# VCO-40106.net
KiCad netlist of a schematic drawn in EAGLE
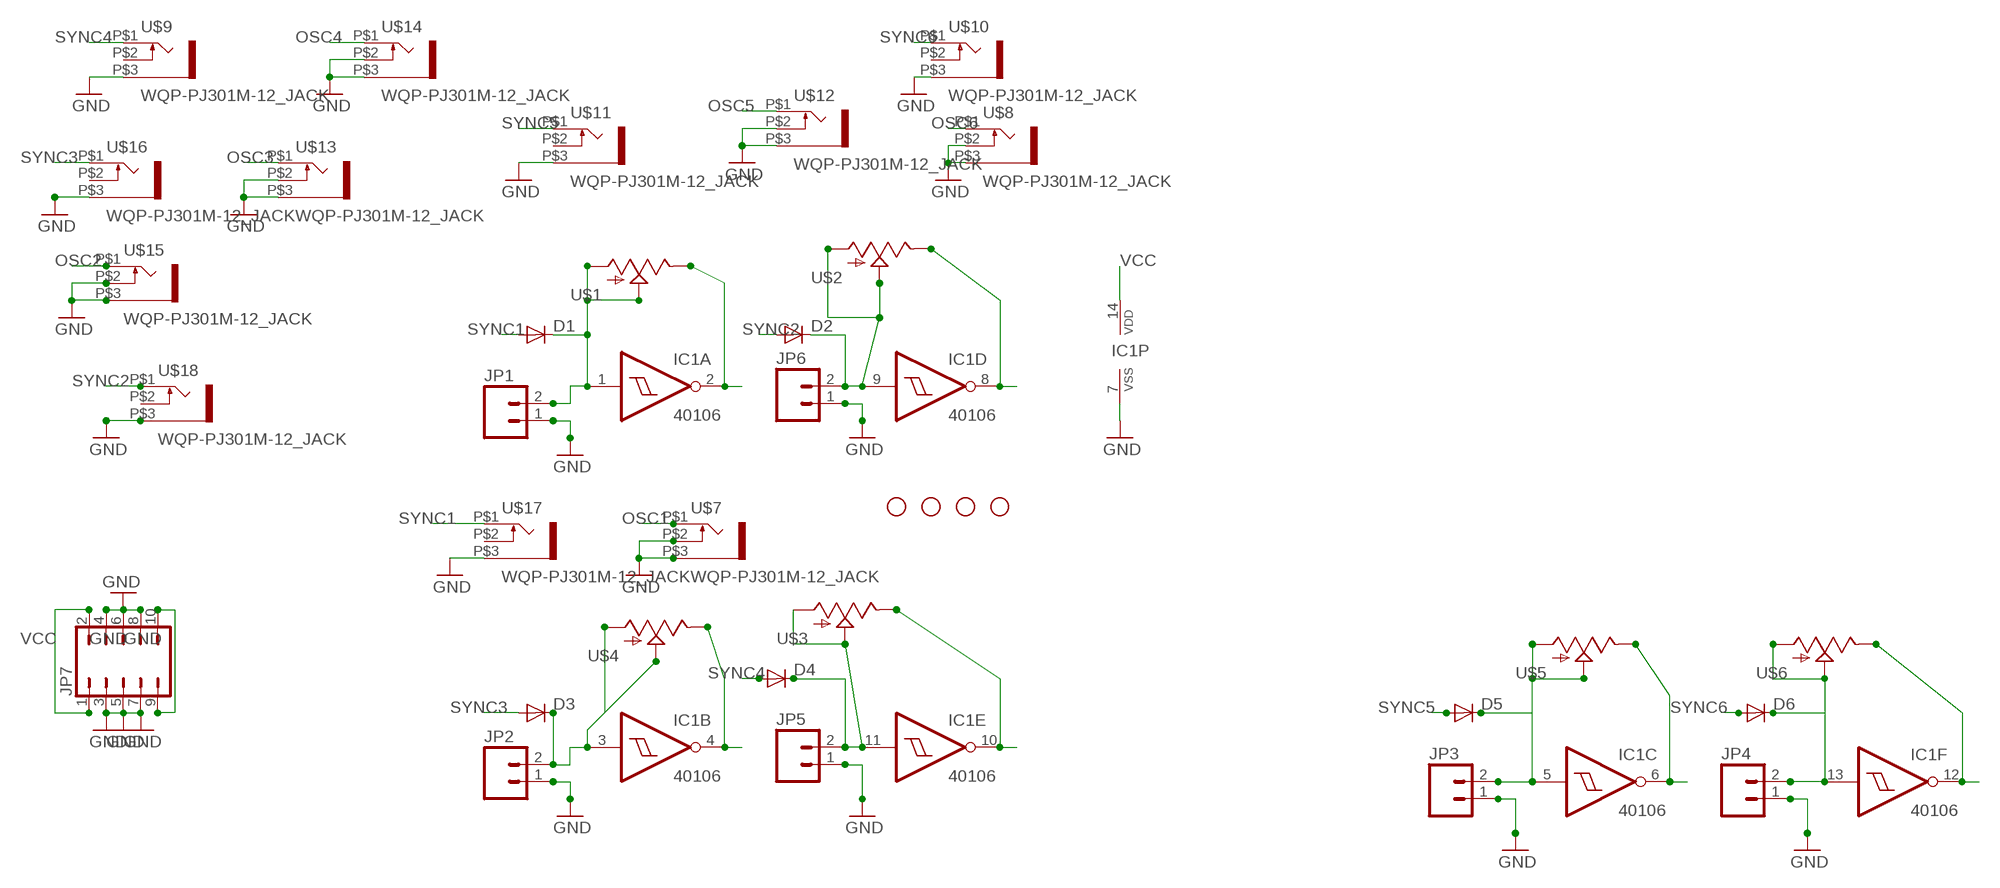
[diagram p0: schematic, sheet 1]

(export (version "E")
  (design (tool "Eeschema 10.0.6"))
  (components
    (comp (ref "D1")
      (value "DIODE1N4148")
      (footprint "eagle-import:DIODE-1N4148")
      (libsource (lib "eagle-import") (part "DIODE1N4148"))
    )
    (comp (ref "D2")
      (value "DIODE1N4148")
      (footprint "eagle-import:DIODE-1N4148")
      (libsource (lib "eagle-import") (part "DIODE1N4148"))
    )
    (comp (ref "D3")
      (value "DIODE1N4148")
      (footprint "eagle-import:DIODE-1N4148")
      (libsource (lib "eagle-import") (part "DIODE1N4148"))
    )
    (comp (ref "D4")
      (value "DIODE1N4148")
      (footprint "eagle-import:DIODE-1N4148")
      (libsource (lib "eagle-import") (part "DIODE1N4148"))
    )
    (comp (ref "D5")
      (value "DIODE1N4148")
      (footprint "eagle-import:DIODE-1N4148")
      (libsource (lib "eagle-import") (part "DIODE1N4148"))
    )
    (comp (ref "D6")
      (value "DIODE1N4148")
      (footprint "eagle-import:DIODE-1N4148")
      (libsource (lib "eagle-import") (part "DIODE1N4148"))
    )
    (comp (ref "IC1")
      (value "40106")
      (footprint "eagle-import:DIL14")
      (libsource (lib "eagle-import") (part "40106N"))
    )
    (comp (ref "JP1")
      (value "M02")
      (footprint "eagle-import:1X02_LONGPADS")
      (libsource (lib "eagle-import") (part "M02"))
    )
    (comp (ref "JP2")
      (value "M02")
      (footprint "eagle-import:1X02_LONGPADS")
      (libsource (lib "eagle-import") (part "M02"))
    )
    (comp (ref "JP3")
      (value "M02")
      (footprint "eagle-import:1X02_LONGPADS")
      (libsource (lib "eagle-import") (part "M02"))
    )
    (comp (ref "JP4")
      (value "M02")
      (footprint "eagle-import:1X02_LONGPADS")
      (libsource (lib "eagle-import") (part "M02"))
    )
    (comp (ref "JP5")
      (value "M02")
      (footprint "eagle-import:1X02_LONGPADS")
      (libsource (lib "eagle-import") (part "M02"))
    )
    (comp (ref "JP6")
      (value "M02")
      (footprint "eagle-import:1X02_LONGPADS")
      (libsource (lib "eagle-import") (part "M02"))
    )
    (comp (ref "JP7")
      (value "JP5Q")
      (footprint "eagle-import:JP5Q")
      (libsource (lib "eagle-import") (part "JP5Q"))
    )
    (comp (ref "JP8")
      (value "STAND-OFF")
      (footprint "eagle-import:STAND-OFF")
      (libsource (lib "eagle-import") (part "STAND-OFF"))
    )
    (comp (ref "JP9")
      (value "STAND-OFF")
      (footprint "eagle-import:STAND-OFF")
      (libsource (lib "eagle-import") (part "STAND-OFF"))
    )
    (comp (ref "JP10")
      (value "STAND-OFF")
      (footprint "eagle-import:STAND-OFF")
      (libsource (lib "eagle-import") (part "STAND-OFF"))
    )
    (comp (ref "JP11")
      (value "STAND-OFF")
      (footprint "eagle-import:STAND-OFF")
      (libsource (lib "eagle-import") (part "STAND-OFF"))
    )
    (comp (ref "U$1")
      (value "POT")
      (footprint "eagle-import:ALPS_POT")
      (libsource (lib "eagle-import") (part "POT"))
    )
    (comp (ref "U$2")
      (value "POT")
      (footprint "eagle-import:ALPS_POT")
      (libsource (lib "eagle-import") (part "POT"))
    )
    (comp (ref "U$3")
      (value "POT")
      (footprint "eagle-import:ALPS_POT")
      (libsource (lib "eagle-import") (part "POT"))
    )
    (comp (ref "U$4")
      (value "POT")
      (footprint "eagle-import:ALPS_POT")
      (libsource (lib "eagle-import") (part "POT"))
    )
    (comp (ref "U$5")
      (value "POT")
      (footprint "eagle-import:ALPS_POT")
      (libsource (lib "eagle-import") (part "POT"))
    )
    (comp (ref "U$6")
      (value "POT")
      (footprint "eagle-import:ALPS_POT")
      (libsource (lib "eagle-import") (part "POT"))
    )
    (comp (ref "U$7")
      (value "WQP-PJ301M-12_JACK")
      (footprint "eagle-import:WQP-PJ301M-12_JACK")
      (libsource (lib "eagle-import") (part "WQP-PJ301M-12_JACK"))
    )
    (comp (ref "U$8")
      (value "WQP-PJ301M-12_JACK")
      (footprint "eagle-import:WQP-PJ301M-12_JACK")
      (libsource (lib "eagle-import") (part "WQP-PJ301M-12_JACK"))
    )
    (comp (ref "U$9")
      (value "WQP-PJ301M-12_JACK")
      (footprint "eagle-import:WQP-PJ301M-12_JACK")
      (libsource (lib "eagle-import") (part "WQP-PJ301M-12_JACK"))
    )
    (comp (ref "U$10")
      (value "WQP-PJ301M-12_JACK")
      (footprint "eagle-import:WQP-PJ301M-12_JACK")
      (libsource (lib "eagle-import") (part "WQP-PJ301M-12_JACK"))
    )
    (comp (ref "U$11")
      (value "WQP-PJ301M-12_JACK")
      (footprint "eagle-import:WQP-PJ301M-12_JACK")
      (libsource (lib "eagle-import") (part "WQP-PJ301M-12_JACK"))
    )
    (comp (ref "U$12")
      (value "WQP-PJ301M-12_JACK")
      (footprint "eagle-import:WQP-PJ301M-12_JACK")
      (libsource (lib "eagle-import") (part "WQP-PJ301M-12_JACK"))
    )
    (comp (ref "U$13")
      (value "WQP-PJ301M-12_JACK")
      (footprint "eagle-import:WQP-PJ301M-12_JACK")
      (libsource (lib "eagle-import") (part "WQP-PJ301M-12_JACK"))
    )
    (comp (ref "U$14")
      (value "WQP-PJ301M-12_JACK")
      (footprint "eagle-import:WQP-PJ301M-12_JACK")
      (libsource (lib "eagle-import") (part "WQP-PJ301M-12_JACK"))
    )
    (comp (ref "U$15")
      (value "WQP-PJ301M-12_JACK")
      (footprint "eagle-import:WQP-PJ301M-12_JACK")
      (libsource (lib "eagle-import") (part "WQP-PJ301M-12_JACK"))
    )
    (comp (ref "U$16")
      (value "WQP-PJ301M-12_JACK")
      (footprint "eagle-import:WQP-PJ301M-12_JACK")
      (libsource (lib "eagle-import") (part "WQP-PJ301M-12_JACK"))
    )
    (comp (ref "U$17")
      (value "WQP-PJ301M-12_JACK")
      (footprint "eagle-import:WQP-PJ301M-12_JACK")
      (libsource (lib "eagle-import") (part "WQP-PJ301M-12_JACK"))
    )
    (comp (ref "U$18")
      (value "WQP-PJ301M-12_JACK")
      (footprint "eagle-import:WQP-PJ301M-12_JACK")
      (libsource (lib "eagle-import") (part "WQP-PJ301M-12_JACK"))
    )
  )
  (nets
    (net (code "1") (name "/OSC1") (class "Default")
      (node (ref "IC1") (pin "2") (pinfunction "O_2") (pintype "output"))
      (node (ref "U$1") (pin "P$1") (pinfunction "E_P$1") (pintype "passive"))
      (node (ref "U$7") (pin "P$1") (pinfunction "2_P$1") (pintype "passive"))
    )
    (net (code "2") (name "/OSC2") (class "Default")
      (node (ref "IC1") (pin "4") (pinfunction "O_4") (pintype "output"))
      (node (ref "U$15") (pin "P$1") (pinfunction "2_P$1") (pintype "passive"))
      (node (ref "U$4") (pin "P$1") (pinfunction "E_P$1") (pintype "passive"))
    )
    (net (code "3") (name "/OSC3") (class "Default")
      (node (ref "IC1") (pin "6") (pinfunction "O_6") (pintype "output"))
      (node (ref "U$13") (pin "P$1") (pinfunction "2_P$1") (pintype "passive"))
      (node (ref "U$5") (pin "P$1") (pinfunction "E_P$1") (pintype "passive"))
    )
    (net (code "4") (name "/OSC4") (class "Default")
      (node (ref "IC1") (pin "8") (pinfunction "O_8") (pintype "output"))
      (node (ref "U$14") (pin "P$1") (pinfunction "2_P$1") (pintype "passive"))
      (node (ref "U$2") (pin "P$1") (pinfunction "E_P$1") (pintype "passive"))
    )
    (net (code "5") (name "/OSC5") (class "Default")
      (node (ref "IC1") (pin "10") (pinfunction "O_10") (pintype "output"))
      (node (ref "U$12") (pin "P$1") (pinfunction "2_P$1") (pintype "passive"))
      (node (ref "U$3") (pin "P$1") (pinfunction "E_P$1") (pintype "passive"))
    )
    (net (code "6") (name "/OSC6") (class "Default")
      (node (ref "IC1") (pin "12") (pinfunction "O_12") (pintype "output"))
      (node (ref "U$6") (pin "P$1") (pinfunction "E_P$1") (pintype "passive"))
      (node (ref "U$8") (pin "P$1") (pinfunction "2_P$1") (pintype "passive"))
    )
    (net (code "7") (name "/SYNC1") (class "Default")
      (node (ref "D1") (pin "A") (pinfunction "A_A") (pintype "passive"))
      (node (ref "U$17") (pin "P$1") (pinfunction "2_P$1") (pintype "passive"))
    )
    (net (code "8") (name "/SYNC2") (class "Default")
      (node (ref "D2") (pin "A") (pinfunction "A_A") (pintype "passive"))
      (node (ref "U$18") (pin "P$1") (pinfunction "2_P$1") (pintype "passive"))
    )
    (net (code "9") (name "/SYNC3") (class "Default")
      (node (ref "D3") (pin "A") (pinfunction "A_A") (pintype "passive"))
      (node (ref "U$16") (pin "P$1") (pinfunction "2_P$1") (pintype "passive"))
    )
    (net (code "10") (name "/SYNC4") (class "Default")
      (node (ref "D4") (pin "A") (pinfunction "A_A") (pintype "passive"))
      (node (ref "U$9") (pin "P$1") (pinfunction "2_P$1") (pintype "passive"))
    )
    (net (code "11") (name "/SYNC5") (class "Default")
      (node (ref "D5") (pin "A") (pinfunction "A_A") (pintype "passive"))
      (node (ref "U$11") (pin "P$1") (pinfunction "2_P$1") (pintype "passive"))
    )
    (net (code "12") (name "/SYNC6") (class "Default")
      (node (ref "D6") (pin "A") (pinfunction "A_A") (pintype "passive"))
      (node (ref "U$10") (pin "P$1") (pinfunction "2_P$1") (pintype "passive"))
    )
    (net (code "13") (name "/VCC") (class "Default")
      (node (ref "IC1") (pin "14") (pinfunction "VDD_14") (pintype "power_in"))
      (node (ref "JP7") (pin "1") (pinfunction "1_1") (pintype "passive"))
      (node (ref "JP7") (pin "2") (pinfunction "2_2") (pintype "passive"))
    )
    (net (code "14") (name "GND") (class "Default")
      (node (ref "IC1") (pin "7") (pinfunction "VSS_7") (pintype "power_in"))
      (node (ref "JP1") (pin "1") (pinfunction "1_1") (pintype "passive"))
      (node (ref "JP2") (pin "1") (pinfunction "1_1") (pintype "passive"))
      (node (ref "JP3") (pin "1") (pinfunction "1_1") (pintype "passive"))
      (node (ref "JP4") (pin "1") (pinfunction "1_1") (pintype "passive"))
      (node (ref "JP5") (pin "1") (pinfunction "1_1") (pintype "passive"))
      (node (ref "JP6") (pin "1") (pinfunction "1_1") (pintype "passive"))
      (node (ref "JP7") (pin "3") (pinfunction "3_3") (pintype "passive"))
      (node (ref "JP7") (pin "4") (pinfunction "4_4") (pintype "passive"))
      (node (ref "JP7") (pin "5") (pinfunction "5_5") (pintype "passive"))
      (node (ref "JP7") (pin "6") (pinfunction "6_6") (pintype "passive"))
      (node (ref "JP7") (pin "7") (pinfunction "7_7") (pintype "passive"))
      (node (ref "JP7") (pin "8") (pinfunction "8_8") (pintype "passive"))
      (node (ref "U$10") (pin "P$3") (pinfunction "1_P$3") (pintype "passive"))
      (node (ref "U$11") (pin "P$3") (pinfunction "1_P$3") (pintype "passive"))
      (node (ref "U$12") (pin "P$2") (pinfunction "3_P$2") (pintype "passive"))
      (node (ref "U$12") (pin "P$3") (pinfunction "1_P$3") (pintype "passive"))
      (node (ref "U$13") (pin "P$2") (pinfunction "3_P$2") (pintype "passive"))
      (node (ref "U$13") (pin "P$3") (pinfunction "1_P$3") (pintype "passive"))
      (node (ref "U$14") (pin "P$2") (pinfunction "3_P$2") (pintype "passive"))
      (node (ref "U$14") (pin "P$3") (pinfunction "1_P$3") (pintype "passive"))
      (node (ref "U$15") (pin "P$2") (pinfunction "3_P$2") (pintype "passive"))
      (node (ref "U$15") (pin "P$3") (pinfunction "1_P$3") (pintype "passive"))
      (node (ref "U$16") (pin "P$3") (pinfunction "1_P$3") (pintype "passive"))
      (node (ref "U$17") (pin "P$3") (pinfunction "1_P$3") (pintype "passive"))
      (node (ref "U$18") (pin "P$3") (pinfunction "1_P$3") (pintype "passive"))
      (node (ref "U$7") (pin "P$2") (pinfunction "3_P$2") (pintype "passive"))
      (node (ref "U$7") (pin "P$3") (pinfunction "1_P$3") (pintype "passive"))
      (node (ref "U$8") (pin "P$2") (pinfunction "3_P$2") (pintype "passive"))
      (node (ref "U$8") (pin "P$3") (pinfunction "1_P$3") (pintype "passive"))
      (node (ref "U$9") (pin "P$3") (pinfunction "1_P$3") (pintype "passive"))
    )
    (net (code "15") (name "Net-(IC1A-I)") (class "Default")
      (node (ref "D1") (pin "C") (pinfunction "C_C") (pintype "passive"))
      (node (ref "IC1") (pin "1") (pinfunction "I_1") (pintype "input"))
      (node (ref "JP1") (pin "2") (pinfunction "2_2") (pintype "passive"))
      (node (ref "U$1") (pin "P$2") (pinfunction "S_P$2") (pintype "passive"))
      (node (ref "U$1") (pin "P$3") (pinfunction "A_P$3") (pintype "passive"))
    )
    (net (code "16") (name "Net-(IC1B-I)") (class "Default")
      (node (ref "D3") (pin "C") (pinfunction "C_C") (pintype "passive"))
      (node (ref "IC1") (pin "3") (pinfunction "I_3") (pintype "input"))
      (node (ref "JP2") (pin "2") (pinfunction "2_2") (pintype "passive"))
      (node (ref "U$4") (pin "P$2") (pinfunction "S_P$2") (pintype "passive"))
      (node (ref "U$4") (pin "P$3") (pinfunction "A_P$3") (pintype "passive"))
    )
    (net (code "17") (name "Net-(IC1C-I)") (class "Default")
      (node (ref "D5") (pin "C") (pinfunction "C_C") (pintype "passive"))
      (node (ref "IC1") (pin "5") (pinfunction "I_5") (pintype "input"))
      (node (ref "JP3") (pin "2") (pinfunction "2_2") (pintype "passive"))
      (node (ref "U$5") (pin "P$2") (pinfunction "S_P$2") (pintype "passive"))
      (node (ref "U$5") (pin "P$3") (pinfunction "A_P$3") (pintype "passive"))
    )
    (net (code "18") (name "Net-(IC1D-I)") (class "Default")
      (node (ref "D2") (pin "C") (pinfunction "C_C") (pintype "passive"))
      (node (ref "IC1") (pin "9") (pinfunction "I_9") (pintype "input"))
      (node (ref "JP6") (pin "2") (pinfunction "2_2") (pintype "passive"))
      (node (ref "U$2") (pin "P$2") (pinfunction "S_P$2") (pintype "passive"))
      (node (ref "U$2") (pin "P$3") (pinfunction "A_P$3") (pintype "passive"))
    )
    (net (code "19") (name "Net-(IC1E-I)") (class "Default")
      (node (ref "D4") (pin "C") (pinfunction "C_C") (pintype "passive"))
      (node (ref "IC1") (pin "11") (pinfunction "I_11") (pintype "input"))
      (node (ref "JP5") (pin "2") (pinfunction "2_2") (pintype "passive"))
      (node (ref "U$3") (pin "P$2") (pinfunction "S_P$2") (pintype "passive"))
      (node (ref "U$3") (pin "P$3") (pinfunction "A_P$3") (pintype "passive"))
    )
    (net (code "20") (name "Net-(IC1F-I)") (class "Default")
      (node (ref "D6") (pin "C") (pinfunction "C_C") (pintype "passive"))
      (node (ref "IC1") (pin "13") (pinfunction "I_13") (pintype "input"))
      (node (ref "JP4") (pin "2") (pinfunction "2_2") (pintype "passive"))
      (node (ref "U$6") (pin "P$2") (pinfunction "S_P$2") (pintype "passive"))
      (node (ref "U$6") (pin "P$3") (pinfunction "A_P$3") (pintype "passive"))
    )
    (net (code "21") (name "Net-(JP7-Pad10)") (class "Default")
      (node (ref "JP7") (pin "10") (pinfunction "10_10") (pintype "passive"))
      (node (ref "JP7") (pin "9") (pinfunction "9_9") (pintype "passive"))
    )
    (net (code "22") (name "unconnected-(U$9-3-PadP$2)") (class "Default")
      (node (ref "U$9") (pin "P$2") (pinfunction "3_P$2") (pintype "passive"))
    )
    (net (code "23") (name "unconnected-(U$10-3-PadP$2)") (class "Default")
      (node (ref "U$10") (pin "P$2") (pinfunction "3_P$2") (pintype "passive"))
    )
    (net (code "24") (name "unconnected-(U$11-3-PadP$2)") (class "Default")
      (node (ref "U$11") (pin "P$2") (pinfunction "3_P$2") (pintype "passive"))
    )
    (net (code "25") (name "unconnected-(U$16-3-PadP$2)") (class "Default")
      (node (ref "U$16") (pin "P$2") (pinfunction "3_P$2") (pintype "passive"))
    )
    (net (code "26") (name "unconnected-(U$17-3-PadP$2)") (class "Default")
      (node (ref "U$17") (pin "P$2") (pinfunction "3_P$2") (pintype "passive"))
    )
    (net (code "27") (name "unconnected-(U$18-3-PadP$2)") (class "Default")
      (node (ref "U$18") (pin "P$2") (pinfunction "3_P$2") (pintype "passive"))
    )
  )
)
